# mvm1a.net
KiCad netlist of a schematic drawn in EAGLE
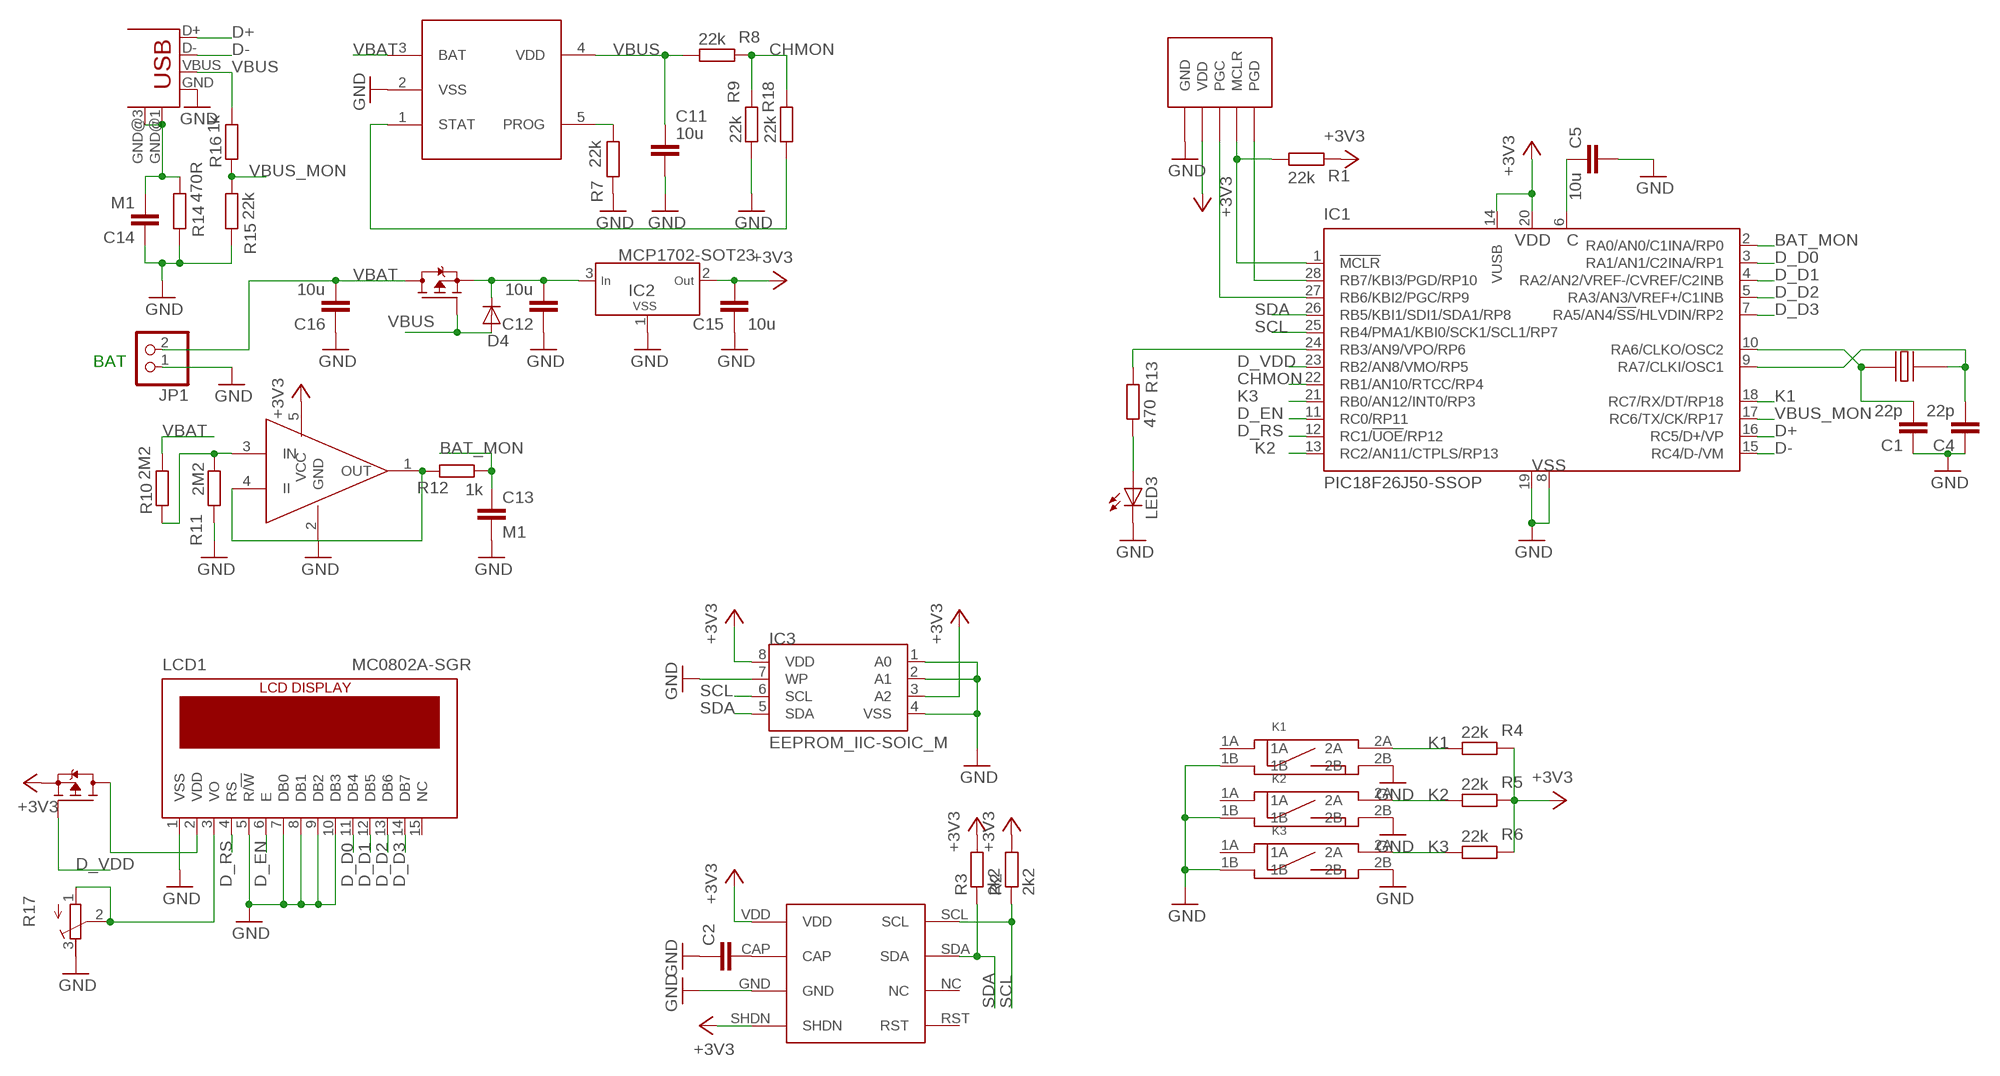
[diagram p0: schematic, sheet 1]

(export (version "E")
  (design (tool "Eeschema 10.0.6"))
  (components
    (comp (ref "C1")
      (value "22p")
      (footprint "eagle-import:0603")
      (libsource (lib "eagle-import") (part "C_0603"))
    )
    (comp (ref "C2")
      (value "C_0603")
      (footprint "eagle-import:0603")
      (libsource (lib "eagle-import") (part "C_0603"))
    )
    (comp (ref "C4")
      (value "22p")
      (footprint "eagle-import:0603")
      (libsource (lib "eagle-import") (part "C_0603"))
    )
    (comp (ref "C5")
      (value "10u")
      (footprint "eagle-import:R0805")
      (libsource (lib "eagle-import") (part "C_0806"))
    )
    (comp (ref "C11")
      (value "10u")
      (footprint "eagle-import:R0805")
      (libsource (lib "eagle-import") (part "C_0806"))
    )
    (comp (ref "C12")
      (value "10u")
      (footprint "eagle-import:R0805")
      (libsource (lib "eagle-import") (part "C_0806"))
    )
    (comp (ref "C13")
      (value "M1")
      (footprint "eagle-import:0603")
      (libsource (lib "eagle-import") (part "C_0603"))
    )
    (comp (ref "C14")
      (value "M1")
      (footprint "eagle-import:0603")
      (libsource (lib "eagle-import") (part "C_0603"))
    )
    (comp (ref "C15")
      (value "10u")
      (footprint "eagle-import:0603")
      (libsource (lib "eagle-import") (part "C_0603"))
    )
    (comp (ref "C16")
      (value "10u")
      (footprint "eagle-import:R0805")
      (libsource (lib "eagle-import") (part "C_0806"))
    )
    (comp (ref "D4")
      (value "DIODE-SOD123")
      (footprint "eagle-import:SOD123")
      (libsource (lib "eagle-import") (part "DIODE-SOD123"))
    )
    (comp (ref "IC1")
      (value "PIC18F26J50-SSOP")
      (footprint "eagle-import:SSOP28")
      (libsource (lib "eagle-import") (part "PIC18F26J50-SSOP"))
    )
    (comp (ref "IC2")
      (value "MCP1702-SOT23")
      (footprint "eagle-import:SOT23")
      (libsource (lib "eagle-import") (part "MCP1702-SOT23"))
    )
    (comp (ref "IC3")
      (value "EEPROM_IIC-SOIC_M")
      (footprint "eagle-import:SO-08_208")
      (libsource (lib "eagle-import") (part "EEPROM_IIC-SOIC_M"))
    )
    (comp (ref "JP1")
      (value "PINHD-1X02_2.54-90°")
      (footprint "eagle-import:1X02_90")
      (libsource (lib "eagle-import") (part "PINHD-1X02_2.54-90°"))
    )
    (comp (ref "K1")
      (value "SWITCH_BD_B")
      (footprint "eagle-import:SW_SMD2")
      (libsource (lib "eagle-import") (part "SWITCH_BD_B"))
    )
    (comp (ref "K2")
      (value "SWITCH_BD_B")
      (footprint "eagle-import:SW_SMD2")
      (libsource (lib "eagle-import") (part "SWITCH_BD_B"))
    )
    (comp (ref "K3")
      (value "SWITCH_BD_B")
      (footprint "eagle-import:SW_SMD2")
      (libsource (lib "eagle-import") (part "SWITCH_BD_B"))
    )
    (comp (ref "LCD1")
      (value "MC0802A-SGR")
      (footprint "eagle-import:MC0802")
      (libsource (lib "eagle-import") (part "MC0802A-SGR"))
    )
    (comp (ref "LED3")
      (value "LEDCHIPLED_0805")
      (footprint "eagle-import:CHIPLED_0805")
      (libsource (lib "eagle-import") (part "LEDCHIPLED_0805"))
    )
    (comp (ref "R1")
      (value "22k")
      (footprint "eagle-import:0603")
      (libsource (lib "eagle-import") (part "R_0603"))
    )
    (comp (ref "R2")
      (value "2k2")
      (footprint "eagle-import:0603")
      (libsource (lib "eagle-import") (part "R_0603"))
    )
    (comp (ref "R3")
      (value "2k2")
      (footprint "eagle-import:0603")
      (libsource (lib "eagle-import") (part "R_0603"))
    )
    (comp (ref "R4")
      (value "22k")
      (footprint "eagle-import:0603")
      (libsource (lib "eagle-import") (part "R_0603"))
    )
    (comp (ref "R5")
      (value "22k")
      (footprint "eagle-import:0603")
      (libsource (lib "eagle-import") (part "R_0603"))
    )
    (comp (ref "R6")
      (value "22k")
      (footprint "eagle-import:0603")
      (libsource (lib "eagle-import") (part "R_0603"))
    )
    (comp (ref "R7")
      (value "22k")
      (footprint "eagle-import:0603")
      (libsource (lib "eagle-import") (part "R_0603"))
    )
    (comp (ref "R8")
      (value "22k")
      (footprint "eagle-import:0603")
      (libsource (lib "eagle-import") (part "R_0603"))
    )
    (comp (ref "R9")
      (value "22k")
      (footprint "eagle-import:0603")
      (libsource (lib "eagle-import") (part "R_0603"))
    )
    (comp (ref "R10")
      (value "2M2")
      (footprint "eagle-import:0603")
      (libsource (lib "eagle-import") (part "R_0603"))
    )
    (comp (ref "R11")
      (value "2M2")
      (footprint "eagle-import:0603")
      (libsource (lib "eagle-import") (part "R_0603"))
    )
    (comp (ref "R12")
      (value "1k")
      (footprint "eagle-import:0603")
      (libsource (lib "eagle-import") (part "R_0603"))
    )
    (comp (ref "R13")
      (value "470")
      (footprint "eagle-import:0603")
      (libsource (lib "eagle-import") (part "R_0603"))
    )
    (comp (ref "R14")
      (value "470R")
      (footprint "eagle-import:0603")
      (libsource (lib "eagle-import") (part "R_0603"))
    )
    (comp (ref "R15")
      (value "22k")
      (footprint "eagle-import:0603")
      (libsource (lib "eagle-import") (part "R_0603"))
    )
    (comp (ref "R16")
      (value "1k")
      (footprint "eagle-import:0603")
      (libsource (lib "eagle-import") (part "R_0603"))
    )
    (comp (ref "R17")
      (value "R-TRIMM4G/J")
      (footprint "eagle-import:RTRIM4G_J")
      (libsource (lib "eagle-import") (part "R-TRIMM4G/J"))
    )
    (comp (ref "R18")
      (value "22k")
      (footprint "eagle-import:0603")
      (libsource (lib "eagle-import") (part "R_0603"))
    )
    (comp (ref "U$1")
      (value "PROGHEAD")
      (footprint "eagle-import:PROGHEAD_2")
      (libsource (lib "eagle-import") (part "PROGHEAD"))
    )
    (comp (ref "U$2")
      (value "BSS84")
      (footprint "eagle-import:SOT23-3")
      (libsource (lib "eagle-import") (part "BSS84"))
    )
    (comp (ref "U$3")
      (value "MCP73831")
      (footprint "eagle-import:SOT23-5")
      (libsource (lib "eagle-import") (part "MCP73831"))
    )
    (comp (ref "U$4")
      (value "BSS84")
      (footprint "eagle-import:SOT23-3")
      (libsource (lib "eagle-import") (part "BSS84"))
    )
    (comp (ref "U$5")
      (value "MCP6001")
      (footprint "eagle-import:SOT23-5")
      (libsource (lib "eagle-import") (part "MCP6001"))
    )
    (comp (ref "U$6")
      (value "MPL115A")
      (footprint "eagle-import:MPL115A")
      (libsource (lib "eagle-import") (part "MPL115A"))
    )
    (comp (ref "USB2")
      (value "USB-MB-S")
      (footprint "eagle-import:USB-MB-S")
      (libsource (lib "eagle-import") (part "USB-MB-S"))
    )
    (comp (ref "X3")
      (value "CRYST_TC26TC38")
      (footprint "eagle-import:TC38")
      (libsource (lib "eagle-import") (part "CRYST_TC26TC38"))
    )
  )
  (nets
    (net (code "1") (name "+3V3") (class "Default")
      (node (ref "C15") (pin "2") (pinfunction "2_2") (pintype "passive"))
      (node (ref "IC1") (pin "14") (pinfunction "VUSB_14") (pintype "bidirectional"))
      (node (ref "IC1") (pin "20") (pinfunction "VDD_20") (pintype "power_in"))
      (node (ref "IC2") (pin "2") (pinfunction "OUT_2") (pintype "output"))
      (node (ref "IC3") (pin "3") (pinfunction "A2_3") (pintype "input"))
      (node (ref "IC3") (pin "8") (pinfunction "VDD_8") (pintype "power_in"))
      (node (ref "R1") (pin "1") (pinfunction "1_1") (pintype "passive"))
      (node (ref "R2") (pin "2") (pinfunction "2_2") (pintype "passive"))
      (node (ref "R3") (pin "2") (pinfunction "2_2") (pintype "passive"))
      (node (ref "R4") (pin "1") (pinfunction "1_1") (pintype "passive"))
      (node (ref "R5") (pin "1") (pinfunction "1_1") (pintype "passive"))
      (node (ref "R6") (pin "1") (pinfunction "1_1") (pintype "passive"))
      (node (ref "U$1") (pin "VDD") (pinfunction "VDD_VDD") (pintype "bidirectional"))
      (node (ref "U$2") (pin "2") (pinfunction "S_2") (pintype "passive"))
      (node (ref "U$5") (pin "5") (pinfunction "VCC_5") (pintype "bidirectional"))
      (node (ref "U$6") (pin "SHDN") (pinfunction "SHDN_SHDN") (pintype "bidirectional"))
      (node (ref "U$6") (pin "VDD") (pinfunction "VDD_VDD") (pintype "bidirectional"))
    )
    (net (code "2") (name "/BAT_MON") (class "Default")
      (node (ref "C13") (pin "1") (pinfunction "1_1") (pintype "passive"))
      (node (ref "IC1") (pin "2") (pinfunction "RA0/AN0/C1INA/RP0_2") (pintype "bidirectional"))
      (node (ref "R12") (pin "1") (pinfunction "1_1") (pintype "passive"))
    )
    (net (code "3") (name "/CHMON") (class "Default")
      (node (ref "IC1") (pin "22") (pinfunction "RB1/AN10/RTCC/RP4_22") (pintype "bidirectional"))
      (node (ref "R18") (pin "1") (pinfunction "1_1") (pintype "passive"))
      (node (ref "R8") (pin "1") (pinfunction "1_1") (pintype "passive"))
      (node (ref "R9") (pin "1") (pinfunction "1_1") (pintype "passive"))
    )
    (net (code "4") (name "/D+") (class "Default")
      (node (ref "IC1") (pin "16") (pinfunction "RC5/D+/VP_16") (pintype "bidirectional"))
      (node (ref "USB2") (pin "D+") (pinfunction "D+_D+") (pintype "bidirectional"))
    )
    (net (code "5") (name "/D-") (class "Default")
      (node (ref "IC1") (pin "15") (pinfunction "RC4/D-/VM_15") (pintype "bidirectional"))
      (node (ref "USB2") (pin "D-") (pinfunction "D-_D-") (pintype "bidirectional"))
    )
    (net (code "6") (name "/D_D0") (class "Default")
      (node (ref "IC1") (pin "3") (pinfunction "RA1/AN1/C2INA/RP1_3") (pintype "bidirectional"))
      (node (ref "LCD1") (pin "11") (pinfunction "DB4_11") (pintype "input"))
    )
    (net (code "7") (name "/D_D1") (class "Default")
      (node (ref "IC1") (pin "4") (pinfunction "RA2/AN2/VREF-/CVREF/C2INB_4") (pintype "bidirectional"))
      (node (ref "LCD1") (pin "12") (pinfunction "DB5_12") (pintype "input"))
    )
    (net (code "8") (name "/D_D2") (class "Default")
      (node (ref "IC1") (pin "5") (pinfunction "RA3/AN3/VREF+/C1INB_5") (pintype "bidirectional"))
      (node (ref "LCD1") (pin "13") (pinfunction "DB6_13") (pintype "input"))
    )
    (net (code "9") (name "/D_D3") (class "Default")
      (node (ref "IC1") (pin "7") (pinfunction "RA5/AN4/~{SS}/HLVDIN/RP2_7") (pintype "bidirectional"))
      (node (ref "LCD1") (pin "14") (pinfunction "DB7_14") (pintype "input"))
    )
    (net (code "10") (name "/D_EN") (class "Default")
      (node (ref "IC1") (pin "11") (pinfunction "RC0/RP11_11") (pintype "bidirectional"))
      (node (ref "LCD1") (pin "6") (pinfunction "E_6") (pintype "input"))
    )
    (net (code "11") (name "/D_RS") (class "Default")
      (node (ref "IC1") (pin "12") (pinfunction "RC1/~{UOE}/RP12_12") (pintype "bidirectional"))
      (node (ref "LCD1") (pin "4") (pinfunction "RS_4") (pintype "input"))
    )
    (net (code "12") (name "/D_VDD") (class "Default")
      (node (ref "IC1") (pin "23") (pinfunction "RB2/AN8/VMO/RP5_23") (pintype "bidirectional"))
      (node (ref "U$2") (pin "1") (pinfunction "G_1") (pintype "passive"))
    )
    (net (code "13") (name "/K1") (class "Default")
      (node (ref "IC1") (pin "18") (pinfunction "RC7/RX/DT/RP18_18") (pintype "bidirectional"))
      (node (ref "K1") (pin "2A") (pinfunction "2A_2A") (pintype "bidirectional"))
      (node (ref "R4") (pin "2") (pinfunction "2_2") (pintype "passive"))
    )
    (net (code "14") (name "/K2") (class "Default")
      (node (ref "IC1") (pin "13") (pinfunction "RC2/AN11/CTPLS/RP13_13") (pintype "bidirectional"))
      (node (ref "K2") (pin "2A") (pinfunction "2A_2A") (pintype "bidirectional"))
      (node (ref "R5") (pin "2") (pinfunction "2_2") (pintype "passive"))
    )
    (net (code "15") (name "/K3") (class "Default")
      (node (ref "IC1") (pin "21") (pinfunction "RB0/AN12/INT0/RP3_21") (pintype "bidirectional"))
      (node (ref "K3") (pin "2A") (pinfunction "2A_2A") (pintype "bidirectional"))
      (node (ref "R6") (pin "2") (pinfunction "2_2") (pintype "passive"))
    )
    (net (code "16") (name "/SCL") (class "Default")
      (node (ref "IC1") (pin "25") (pinfunction "RB4/PMA1/KBI0/SCK1/SCL1/RP7_25") (pintype "bidirectional"))
      (node (ref "IC3") (pin "6") (pinfunction "SCL_6") (pintype "input"))
      (node (ref "R2") (pin "1") (pinfunction "1_1") (pintype "passive"))
      (node (ref "U$6") (pin "SCL") (pinfunction "SCL_SCL") (pintype "bidirectional"))
    )
    (net (code "17") (name "/SDA") (class "Default")
      (node (ref "IC1") (pin "26") (pinfunction "RB5/KBI1/SDI1/SDA1/RP8_26") (pintype "bidirectional"))
      (node (ref "IC3") (pin "5") (pinfunction "SDA_5") (pintype "input"))
      (node (ref "R3") (pin "1") (pinfunction "1_1") (pintype "passive"))
      (node (ref "U$6") (pin "SDA") (pinfunction "SDA_SDA") (pintype "bidirectional"))
    )
    (net (code "18") (name "/VBAT") (class "Default")
      (node (ref "C16") (pin "2") (pinfunction "2_2") (pintype "passive"))
      (node (ref "JP1") (pin "2") (pinfunction "2_2") (pintype "passive"))
      (node (ref "R10") (pin "2") (pinfunction "2_2") (pintype "passive"))
      (node (ref "U$3") (pin "3") (pinfunction "BAT_3") (pintype "bidirectional"))
      (node (ref "U$4") (pin "3") (pinfunction "D_3") (pintype "passive"))
    )
    (net (code "19") (name "/VBUS") (class "Default")
      (node (ref "C11") (pin "1") (pinfunction "1_1") (pintype "passive"))
      (node (ref "D4") (pin "A") (pinfunction "A_A") (pintype "passive"))
      (node (ref "R16") (pin "2") (pinfunction "2_2") (pintype "passive"))
      (node (ref "R8") (pin "2") (pinfunction "2_2") (pintype "passive"))
      (node (ref "U$3") (pin "4") (pinfunction "VDD_4") (pintype "bidirectional"))
      (node (ref "U$4") (pin "1") (pinfunction "G_1") (pintype "passive"))
      (node (ref "USB2") (pin "VBUS") (pinfunction "VBUS_VBUS") (pintype "bidirectional"))
    )
    (net (code "20") (name "/VBUS_MON") (class "Default")
      (node (ref "IC1") (pin "17") (pinfunction "RC6/TX/CK/RP17_17") (pintype "bidirectional"))
      (node (ref "R15") (pin "2") (pinfunction "2_2") (pintype "passive"))
      (node (ref "R16") (pin "1") (pinfunction "1_1") (pintype "passive"))
    )
    (net (code "21") (name "GND") (class "Default")
      (node (ref "C1") (pin "1") (pinfunction "1_1") (pintype "passive"))
      (node (ref "C11") (pin "2") (pinfunction "2_2") (pintype "passive"))
      (node (ref "C12") (pin "1") (pinfunction "1_1") (pintype "passive"))
      (node (ref "C13") (pin "2") (pinfunction "2_2") (pintype "passive"))
      (node (ref "C14") (pin "1") (pinfunction "1_1") (pintype "passive"))
      (node (ref "C15") (pin "1") (pinfunction "1_1") (pintype "passive"))
      (node (ref "C16") (pin "1") (pinfunction "1_1") (pintype "passive"))
      (node (ref "C2") (pin "1") (pinfunction "1_1") (pintype "passive"))
      (node (ref "C4") (pin "1") (pinfunction "1_1") (pintype "passive"))
      (node (ref "C5") (pin "2") (pinfunction "2_2") (pintype "passive"))
      (node (ref "IC1") (pin "19") (pinfunction "VSS_19") (pintype "power_in"))
      (node (ref "IC1") (pin "8") (pinfunction "VSS_8") (pintype "power_in"))
      (node (ref "IC2") (pin "1") (pinfunction "VSS_1") (pintype "input"))
      (node (ref "IC3") (pin "1") (pinfunction "A0_1") (pintype "input"))
      (node (ref "IC3") (pin "2") (pinfunction "A1_2") (pintype "input"))
      (node (ref "IC3") (pin "4") (pinfunction "VSS_4") (pintype "power_in"))
      (node (ref "IC3") (pin "7") (pinfunction "WP_7") (pintype "input"))
      (node (ref "JP1") (pin "1") (pinfunction "1_1") (pintype "passive"))
      (node (ref "K1") (pin "1B") (pinfunction "1B_1B") (pintype "bidirectional"))
      (node (ref "K1") (pin "2B") (pinfunction "2B_2B") (pintype "bidirectional"))
      (node (ref "K2") (pin "1B") (pinfunction "1B_1B") (pintype "bidirectional"))
      (node (ref "K2") (pin "2B") (pinfunction "2B_2B") (pintype "bidirectional"))
      (node (ref "K3") (pin "1B") (pinfunction "1B_1B") (pintype "bidirectional"))
      (node (ref "K3") (pin "2B") (pinfunction "2B_2B") (pintype "bidirectional"))
      (node (ref "LCD1") (pin "1") (pinfunction "VSS_1") (pintype "power_in"))
      (node (ref "LCD1") (pin "10") (pinfunction "DB3_10") (pintype "input"))
      (node (ref "LCD1") (pin "5") (pinfunction "R/~{W}_5") (pintype "input"))
      (node (ref "LCD1") (pin "7") (pinfunction "DB0_7") (pintype "input"))
      (node (ref "LCD1") (pin "8") (pinfunction "DB1_8") (pintype "input"))
      (node (ref "LCD1") (pin "9") (pinfunction "DB2_9") (pintype "input"))
      (node (ref "LED3") (pin "C") (pinfunction "C_C") (pintype "passive"))
      (node (ref "R11") (pin "2") (pinfunction "2_2") (pintype "passive"))
      (node (ref "R14") (pin "1") (pinfunction "1_1") (pintype "passive"))
      (node (ref "R15") (pin "1") (pinfunction "1_1") (pintype "passive"))
      (node (ref "R17") (pin "3") (pinfunction "A_3") (pintype "passive"))
      (node (ref "R7") (pin "1") (pinfunction "1_1") (pintype "passive"))
      (node (ref "R9") (pin "2") (pinfunction "2_2") (pintype "passive"))
      (node (ref "U$1") (pin "GND") (pinfunction "GND_GND") (pintype "bidirectional"))
      (node (ref "U$3") (pin "2") (pinfunction "VSS_2") (pintype "bidirectional"))
      (node (ref "U$5") (pin "2") (pinfunction "GND_2") (pintype "bidirectional"))
      (node (ref "U$6") (pin "GND") (pinfunction "GND_GND") (pintype "bidirectional"))
      (node (ref "USB2") (pin "GND") (pinfunction "GND_GND") (pintype "bidirectional"))
    )
    (net (code "22") (name "Net-(C2-Pad2)") (class "Default")
      (node (ref "C2") (pin "2") (pinfunction "2_2") (pintype "passive"))
      (node (ref "U$6") (pin "CAP") (pinfunction "CAP_CAP") (pintype "bidirectional"))
    )
    (net (code "23") (name "Net-(C14-Pad2)") (class "Default")
      (node (ref "C14") (pin "2") (pinfunction "2_2") (pintype "passive"))
      (node (ref "R14") (pin "2") (pinfunction "2_2") (pintype "passive"))
      (node (ref "USB2") (pin "GND@1") (pinfunction "GND_GND@1") (pintype "bidirectional"))
      (node (ref "USB2") (pin "GND@3") (pinfunction "GND_GND@3") (pintype "bidirectional"))
    )
    (net (code "24") (name "Net-(IC1-RA6{slash}CLKO{slash}OSC2)") (class "Default")
      (node (ref "C1") (pin "2") (pinfunction "2_2") (pintype "passive"))
      (node (ref "IC1") (pin "10") (pinfunction "RA6/CLKO/OSC2_10") (pintype "output"))
      (node (ref "X3") (pin "P$1") (pinfunction "P$1_P$1") (pintype "bidirectional"))
    )
    (net (code "25") (name "Net-(IC1-RA7{slash}CLKI{slash}OSC1)") (class "Default")
      (node (ref "C4") (pin "2") (pinfunction "2_2") (pintype "passive"))
      (node (ref "IC1") (pin "9") (pinfunction "RA7/CLKI/OSC1_9") (pintype "input"))
      (node (ref "X3") (pin "P$2") (pinfunction "P$2_P$2") (pintype "bidirectional"))
    )
    (net (code "26") (name "Net-(IC1-RB3{slash}AN9{slash}VPO{slash}RP6)") (class "Default")
      (node (ref "IC1") (pin "24") (pinfunction "RB3/AN9/VPO/RP6_24") (pintype "bidirectional"))
      (node (ref "R13") (pin "2") (pinfunction "2_2") (pintype "passive"))
    )
    (net (code "27") (name "Net-(IC1-RB6{slash}KBI2{slash}PGC{slash}RP9)") (class "Default")
      (node (ref "IC1") (pin "27") (pinfunction "RB6/KBI2/PGC/RP9_27") (pintype "bidirectional"))
      (node (ref "U$1") (pin "PGC") (pinfunction "PGC_PGC") (pintype "bidirectional"))
    )
    (net (code "28") (name "Net-(IC1-RB7{slash}KBI3{slash}PGD{slash}RP10)") (class "Default")
      (node (ref "IC1") (pin "28") (pinfunction "RB7/KBI3/PGD/RP10_28") (pintype "bidirectional"))
      (node (ref "U$1") (pin "PGD") (pinfunction "PGD_PGD") (pintype "bidirectional"))
    )
    (net (code "29") (name "Net-(IC1-VDDCORE{slash}VCAP)") (class "Default")
      (node (ref "C5") (pin "1") (pinfunction "1_1") (pintype "passive"))
      (node (ref "IC1") (pin "6") (pinfunction "VDDCORE/VCAP_6") (pintype "power_in"))
    )
    (net (code "30") (name "Net-(IC1-~{MCLR})") (class "Default")
      (node (ref "IC1") (pin "1") (pinfunction "~{MCLR}_1") (pintype "input"))
      (node (ref "R1") (pin "2") (pinfunction "2_2") (pintype "passive"))
      (node (ref "U$1") (pin "MCLR") (pinfunction "MCLR_MCLR") (pintype "bidirectional"))
    )
    (net (code "31") (name "Net-(IC2-IN)") (class "Default")
      (node (ref "C12") (pin "2") (pinfunction "2_2") (pintype "passive"))
      (node (ref "D4") (pin "C") (pinfunction "C_C") (pintype "passive"))
      (node (ref "IC2") (pin "3") (pinfunction "IN_3") (pintype "input"))
      (node (ref "U$4") (pin "2") (pinfunction "S_2") (pintype "passive"))
    )
    (net (code "32") (name "Net-(LCD1-VDD)") (class "Default")
      (node (ref "LCD1") (pin "2") (pinfunction "VDD_2") (pintype "power_in"))
      (node (ref "U$2") (pin "3") (pinfunction "D_3") (pintype "passive"))
    )
    (net (code "33") (name "Net-(LCD1-VO)") (class "Default")
      (node (ref "LCD1") (pin "3") (pinfunction "VO_3") (pintype "input"))
      (node (ref "R17") (pin "1") (pinfunction "E_1") (pintype "passive"))
      (node (ref "R17") (pin "2") (pinfunction "S_2") (pintype "passive"))
    )
    (net (code "34") (name "Net-(LED3-PadA)") (class "Default")
      (node (ref "LED3") (pin "A") (pinfunction "A_A") (pintype "passive"))
      (node (ref "R13") (pin "1") (pinfunction "1_1") (pintype "passive"))
    )
    (net (code "35") (name "Net-(U$3-PROG)") (class "Default")
      (node (ref "R7") (pin "2") (pinfunction "2_2") (pintype "passive"))
      (node (ref "U$3") (pin "5") (pinfunction "PROG_5") (pintype "bidirectional"))
    )
    (net (code "36") (name "Net-(U$3-STAT)") (class "Default")
      (node (ref "R18") (pin "2") (pinfunction "2_2") (pintype "passive"))
      (node (ref "U$3") (pin "1") (pinfunction "STAT_1") (pintype "bidirectional"))
    )
    (net (code "37") (name "Net-(U$5-II)") (class "Default")
      (node (ref "R12") (pin "2") (pinfunction "2_2") (pintype "passive"))
      (node (ref "U$5") (pin "1") (pinfunction "OUT_1") (pintype "bidirectional"))
      (node (ref "U$5") (pin "4") (pinfunction "II_4") (pintype "bidirectional"))
    )
    (net (code "38") (name "Net-(U$5-IN)") (class "Default")
      (node (ref "R10") (pin "1") (pinfunction "1_1") (pintype "passive"))
      (node (ref "R11") (pin "1") (pinfunction "1_1") (pintype "passive"))
      (node (ref "U$5") (pin "3") (pinfunction "IN_3") (pintype "bidirectional"))
    )
    (net (code "39") (name "unconnected-(K1-Pad1A)") (class "Default")
      (node (ref "K1") (pin "1A") (pinfunction "1A_1A") (pintype "bidirectional"))
    )
    (net (code "40") (name "unconnected-(K2-Pad1A)") (class "Default")
      (node (ref "K2") (pin "1A") (pinfunction "1A_1A") (pintype "bidirectional"))
    )
    (net (code "41") (name "unconnected-(K3-Pad1A)") (class "Default")
      (node (ref "K3") (pin "1A") (pinfunction "1A_1A") (pintype "bidirectional"))
    )
    (net (code "42") (name "unconnected-(LCD1-NC-Pad15)") (class "Default")
      (node (ref "LCD1") (pin "15") (pinfunction "NC_15") (pintype "input"))
    )
    (net (code "43") (name "unconnected-(U$6-PadNC)") (class "Default")
      (node (ref "U$6") (pin "NC") (pinfunction "NC_NC") (pintype "bidirectional"))
    )
    (net (code "44") (name "unconnected-(U$6-PadRST)") (class "Default")
      (node (ref "U$6") (pin "RST") (pinfunction "RST_RST") (pintype "bidirectional"))
    )
  )
)
